# usb.net
KiCad netlist of a schematic drawn in Altium Designer
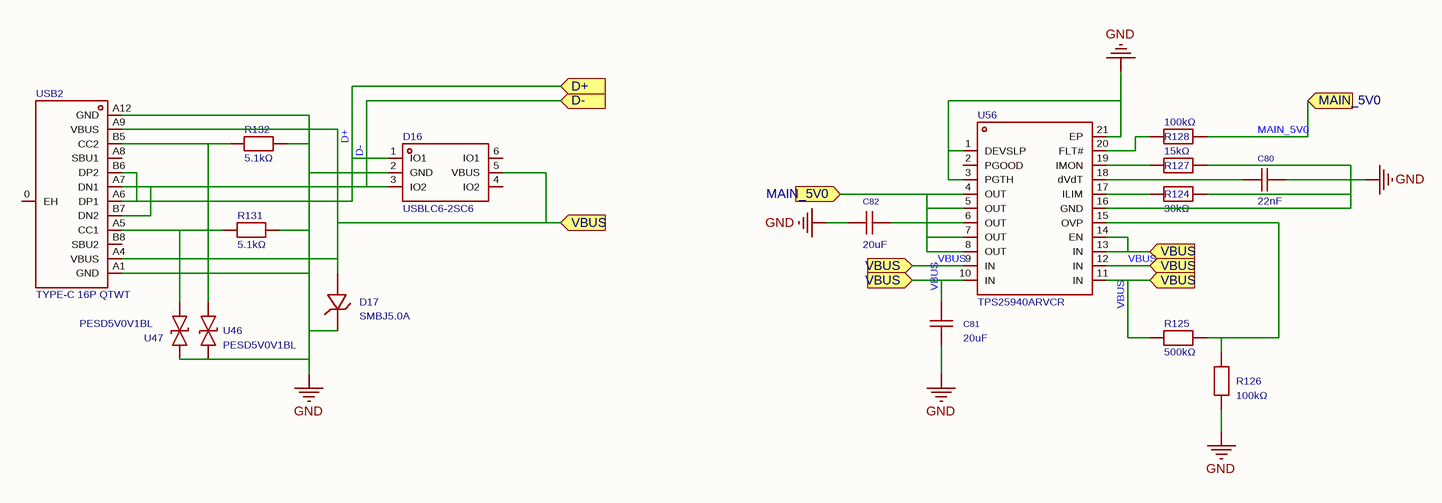
[diagram p0: usb.schdoc]

(export (version "E")
  (design (tool "Eeschema 10.0.6"))
  (components
    (comp (ref "C80")
      (value "22nF")
      (footprint "C0603")
      (description "Capacitance:22nF Tolerance:±10% Tolerance:±10% Voltage Rating:50V Temperature Coefficient:X7R")
      (fields
        (field (name "MANUFACTURER PART") "CL10B223KB8NNNC")
        (field (name "MANUFACTURER") "SAMSUNG(三星)")
      )
      (libsource (lib "altium-import") (part "root_0_CL10B223KB8NNNC_"))
    )
    (comp (ref "C81")
      (value "20uF")
      (footprint "C0603")
      (description "Capacitance:22nF Tolerance:±10% Tolerance:±10% Voltage Rating:50V Temperature Coefficient:X7R")
      (fields
        (field (name "MANUFACTURER PART") "CL10B223KB8NNNC")
        (field (name "MANUFACTURER") "SAMSUNG(三星)")
      )
      (libsource (lib "altium-import") (part "root_1_CL10B223KB8NNNC_"))
    )
    (comp (ref "C82")
      (value "20uF")
      (footprint "C0603")
      (description "Capacitance:22nF Tolerance:±10% Tolerance:±10% Voltage Rating:50V Temperature Coefficient:X7R")
      (fields
        (field (name "MANUFACTURER PART") "CL10B223KB8NNNC")
        (field (name "MANUFACTURER") "SAMSUNG(三星)")
      )
      (libsource (lib "altium-import") (part "root_2_CL10B223KB8NNNC_"))
    )
    (comp (ref "D16")
      (value "USBLC6-2SC6")
      (footprint "SOT-23-6_L2.9-W1.6-P0.95-LS2.8-BL")
      (fields (field (name "MANUFACTURER") "TECH PUBLIC(台舟)"))
      (libsource (lib "altium-import") (part "root_0_USBLC6-2SC6_C2827654_"))
    )
    (comp (ref "D17")
      (value "SMBJ5.0A")
      (footprint "SMB_L4.6-W3.6-LS5.3-RD")
      (fields (field (name "MANUFACTURER") "Littelfuse(美国力特)"))
      (libsource (lib "altium-import") (part "root_1_SMBJ5.0A_C83333_"))
    )
    (comp (ref "R124")
      (value "30kΩ")
      (footprint "R0402")
      (fields
        (field (name "MANUFACTURER") "FOJAN(富捷)")
        (field (name "MANUFACTURERPART") "FRC0402F3002TS")
        (field (name "TOLERANCE") "±1%")
      )
      (libsource (lib "altium-import") (part "root_0_FRC0402F3002TS_"))
    )
    (comp (ref "R125")
      (value "500kΩ")
      (footprint "R0402")
      (fields
        (field (name "MANUFACTURER") "FOJAN(富捷)")
        (field (name "MANUFACTURERPART") "FRC0402F3002TS")
        (field (name "TOLERANCE") "±1%")
      )
      (libsource (lib "altium-import") (part "root_0_FRC0402F3002TS_"))
    )
    (comp (ref "R126")
      (value "100kΩ")
      (footprint "R0402")
      (fields
        (field (name "MANUFACTURER") "FOJAN(富捷)")
        (field (name "MANUFACTURERPART") "FRC0402F3002TS")
        (field (name "TOLERANCE") "±1%")
      )
      (libsource (lib "altium-import") (part "root_3_FRC0402F3002TS_"))
    )
    (comp (ref "R127")
      (value "15kΩ")
      (footprint "R0402")
      (fields
        (field (name "MANUFACTURER") "FOJAN(富捷)")
        (field (name "MANUFACTURERPART") "FRC0402F3002TS")
        (field (name "TOLERANCE") "±1%")
      )
      (libsource (lib "altium-import") (part "root_0_FRC0402F3002TS_"))
    )
    (comp (ref "R128")
      (value "100kΩ")
      (footprint "R0402")
      (fields
        (field (name "MANUFACTURER") "FOJAN(富捷)")
        (field (name "MANUFACTURERPART") "FRC0402F3002TS")
        (field (name "TOLERANCE") "±1%")
      )
      (libsource (lib "altium-import") (part "root_0_FRC0402F3002TS_"))
    )
    (comp (ref "R131")
      (value "5.1kΩ")
      (footprint "R0402")
      (fields
        (field (name "MANUFACTURER") "FOJAN(富捷)")
        (field (name "MANUFACTURERPART") "FRC0402F3002TS")
        (field (name "TOLERANCE") "±1%")
      )
      (libsource (lib "altium-import") (part "root_2_FRC0402F3002TS_"))
    )
    (comp (ref "R132")
      (value "5.1kΩ")
      (footprint "R0402")
      (fields
        (field (name "MANUFACTURER") "FOJAN(富捷)")
        (field (name "MANUFACTURERPART") "FRC0402F3002TS")
        (field (name "TOLERANCE") "±1%")
      )
      (libsource (lib "altium-import") (part "root_2_FRC0402F3002TS_"))
    )
    (comp (ref "U46")
      (value "PESD5V0V1BL")
      (footprint "DFN1006-2L-BI")
      (fields (field (name "MANUFACTURER") "TECH PUBLIC(台舟)"))
      (libsource (lib "altium-import") (part "root_3_PESD5V0V1BL_"))
    )
    (comp (ref "U47")
      (value "PESD5V0V1BL")
      (footprint "DFN1006-2L-BI")
      (fields (field (name "MANUFACTURER") "TECH PUBLIC(台舟)"))
      (libsource (lib "altium-import") (part "root_3_PESD5V0V1BL_"))
    )
    (comp (ref "U56")
      (value "TPS25940ARVCR")
      (footprint "WQFN-20_L4.0-W3.0-P0.50-BL-EP")
      (fields (field (name "MANUFACTURER") "TI(德州仪器)"))
      (libsource (lib "altium-import") (part "root_0_TPS25940ARVCR_"))
    )
    (comp (ref "USB2")
      (value "TYPE-C 16P QTWT")
      (footprint "USB-TYPE-C-SMD_TYPE-C-16P-QTWT")
      (fields (field (name "MANUFACTURER") "SHOU HAN(首韩)"))
      (libsource (lib "altium-import") (part "root_0_mirrored_TYPE-C 16P QTWT_"))
    )
  )
  (nets
    (net (code "1") (name "/D+") (class "Default")
      (node (ref "D16") (pin "1") (pinfunction "IO1_1") (pintype "passive"))
      (node (ref "USB2") (pin "A6") (pinfunction "DP1_A6") (pintype "passive"))
      (node (ref "USB2") (pin "B6") (pinfunction "DP2_B6") (pintype "passive"))
    )
    (net (code "2") (name "/D-") (class "Default")
      (node (ref "D16") (pin "3") (pinfunction "IO2_3") (pintype "passive"))
      (node (ref "USB2") (pin "A7") (pinfunction "DN1_A7") (pintype "passive"))
      (node (ref "USB2") (pin "B7") (pinfunction "DN2_B7") (pintype "passive"))
    )
    (net (code "3") (name "/MAIN_5V0") (class "Default")
      (node (ref "C82") (pin "1") (pinfunction "1_1") (pintype "passive"))
      (node (ref "R128") (pin "2") (pinfunction "2_2") (pintype "passive"))
      (node (ref "U56") (pin "4") (pinfunction "OUT_4") (pintype "passive"))
      (node (ref "U56") (pin "5") (pinfunction "OUT_5") (pintype "passive"))
      (node (ref "U56") (pin "6") (pinfunction "OUT_6") (pintype "passive"))
      (node (ref "U56") (pin "7") (pinfunction "OUT_7") (pintype "passive"))
      (node (ref "U56") (pin "8") (pinfunction "OUT_8") (pintype "passive"))
    )
    (net (code "4") (name "/VBUS") (class "Default")
      (node (ref "C81") (pin "2") (pinfunction "2_2") (pintype "passive"))
      (node (ref "D16") (pin "5") (pinfunction "VBUS_5") (pintype "passive"))
      (node (ref "D17") (pin "2") (pinfunction "2_2") (pintype "passive"))
      (node (ref "R125") (pin "1") (pinfunction "1_1") (pintype "passive"))
      (node (ref "U56") (pin "10") (pinfunction "IN_10") (pintype "passive"))
      (node (ref "U56") (pin "11") (pinfunction "IN_11") (pintype "passive"))
      (node (ref "U56") (pin "12") (pinfunction "IN_12") (pintype "passive"))
      (node (ref "U56") (pin "13") (pinfunction "IN_13") (pintype "passive"))
      (node (ref "U56") (pin "14") (pinfunction "EN_14") (pintype "passive"))
      (node (ref "U56") (pin "9") (pinfunction "IN_9") (pintype "passive"))
      (node (ref "USB2") (pin "A4") (pinfunction "VBUS_A4") (pintype "passive"))
      (node (ref "USB2") (pin "A9") (pinfunction "VBUS_A9") (pintype "passive"))
    )
    (net (code "5") (name "GND") (class "Default")
      (node (ref "C80") (pin "2") (pinfunction "2_2") (pintype "passive"))
      (node (ref "C81") (pin "1") (pinfunction "1_1") (pintype "passive"))
      (node (ref "C82") (pin "2") (pinfunction "2_2") (pintype "passive"))
      (node (ref "D16") (pin "2") (pinfunction "GND_2") (pintype "passive"))
      (node (ref "D17") (pin "1") (pinfunction "1_1") (pintype "passive"))
      (node (ref "R124") (pin "2") (pinfunction "2_2") (pintype "passive"))
      (node (ref "R126") (pin "2") (pinfunction "2_2") (pintype "passive"))
      (node (ref "R127") (pin "2") (pinfunction "2_2") (pintype "passive"))
      (node (ref "R131") (pin "1") (pinfunction "1_1") (pintype "passive"))
      (node (ref "R132") (pin "1") (pinfunction "1_1") (pintype "passive"))
      (node (ref "U46") (pin "2") (pinfunction "2_2") (pintype "passive"))
      (node (ref "U47") (pin "2") (pinfunction "2_2") (pintype "passive"))
      (node (ref "U56") (pin "1") (pinfunction "DEVSLP_1") (pintype "passive"))
      (node (ref "U56") (pin "16") (pinfunction "GND_16") (pintype "passive"))
      (node (ref "U56") (pin "21") (pinfunction "EP_21") (pintype "passive"))
      (node (ref "U56") (pin "3") (pinfunction "PGTH_3") (pintype "passive"))
      (node (ref "USB2") (pin "A1") (pinfunction "GND_A1") (pintype "passive"))
      (node (ref "USB2") (pin "A12") (pinfunction "GND_A12") (pintype "passive"))
    )
    (net (code "6") (name "Net-(U56-FLT#)") (class "Default")
      (node (ref "R128") (pin "1") (pinfunction "1_1") (pintype "passive"))
      (node (ref "U56") (pin "20") (pinfunction "FLT#_20") (pintype "passive"))
    )
    (net (code "7") (name "Net-(U56-ILIM)") (class "Default")
      (node (ref "R124") (pin "1") (pinfunction "1_1") (pintype "passive"))
      (node (ref "U56") (pin "17") (pinfunction "ILIM_17") (pintype "passive"))
    )
    (net (code "8") (name "Net-(U56-IMON)") (class "Default")
      (node (ref "R127") (pin "1") (pinfunction "1_1") (pintype "passive"))
      (node (ref "U56") (pin "19") (pinfunction "IMON_19") (pintype "passive"))
    )
    (net (code "9") (name "Net-(U56-OVP)") (class "Default")
      (node (ref "R125") (pin "2") (pinfunction "2_2") (pintype "passive"))
      (node (ref "R126") (pin "1") (pinfunction "1_1") (pintype "passive"))
      (node (ref "U56") (pin "15") (pinfunction "OVP_15") (pintype "passive"))
    )
    (net (code "10") (name "Net-(U56-dVdT)") (class "Default")
      (node (ref "C80") (pin "1") (pinfunction "1_1") (pintype "passive"))
      (node (ref "U56") (pin "18") (pinfunction "dVdT_18") (pintype "passive"))
    )
    (net (code "11") (name "Net-(USB2-CC1)") (class "Default")
      (node (ref "R131") (pin "2") (pinfunction "2_2") (pintype "passive"))
      (node (ref "U47") (pin "1") (pinfunction "1_1") (pintype "passive"))
      (node (ref "USB2") (pin "A5") (pinfunction "CC1_A5") (pintype "passive"))
    )
    (net (code "12") (name "Net-(USB2-CC2)") (class "Default")
      (node (ref "R132") (pin "2") (pinfunction "2_2") (pintype "passive"))
      (node (ref "U46") (pin "1") (pinfunction "1_1") (pintype "passive"))
      (node (ref "USB2") (pin "B5") (pinfunction "CC2_B5") (pintype "passive"))
    )
    (net (code "13") (name "unconnected-(D16-IO1-Pad6)") (class "Default")
      (node (ref "D16") (pin "6") (pinfunction "IO1_6") (pintype "passive"))
    )
    (net (code "14") (name "unconnected-(D16-IO2-Pad4)") (class "Default")
      (node (ref "D16") (pin "4") (pinfunction "IO2_4") (pintype "passive"))
    )
    (net (code "15") (name "unconnected-(U56-PGOOD-Pad2)") (class "Default")
      (node (ref "U56") (pin "2") (pinfunction "PGOOD_2") (pintype "passive"))
    )
    (net (code "16") (name "unconnected-(USB2-EH-Pad0)") (class "Default")
      (node (ref "USB2") (pin "0") (pinfunction "EH_0") (pintype "passive"))
    )
    (net (code "17") (name "unconnected-(USB2-SBU1-PadA8)") (class "Default")
      (node (ref "USB2") (pin "A8") (pinfunction "SBU1_A8") (pintype "passive"))
    )
    (net (code "18") (name "unconnected-(USB2-SBU2-PadB8)") (class "Default")
      (node (ref "USB2") (pin "B8") (pinfunction "SBU2_B8") (pintype "passive"))
    )
  )
)
